# LEDChaser_Schemtic-P1_2025-11-05.net
KiCad netlist of a schematic drawn in EasyEDA Pro
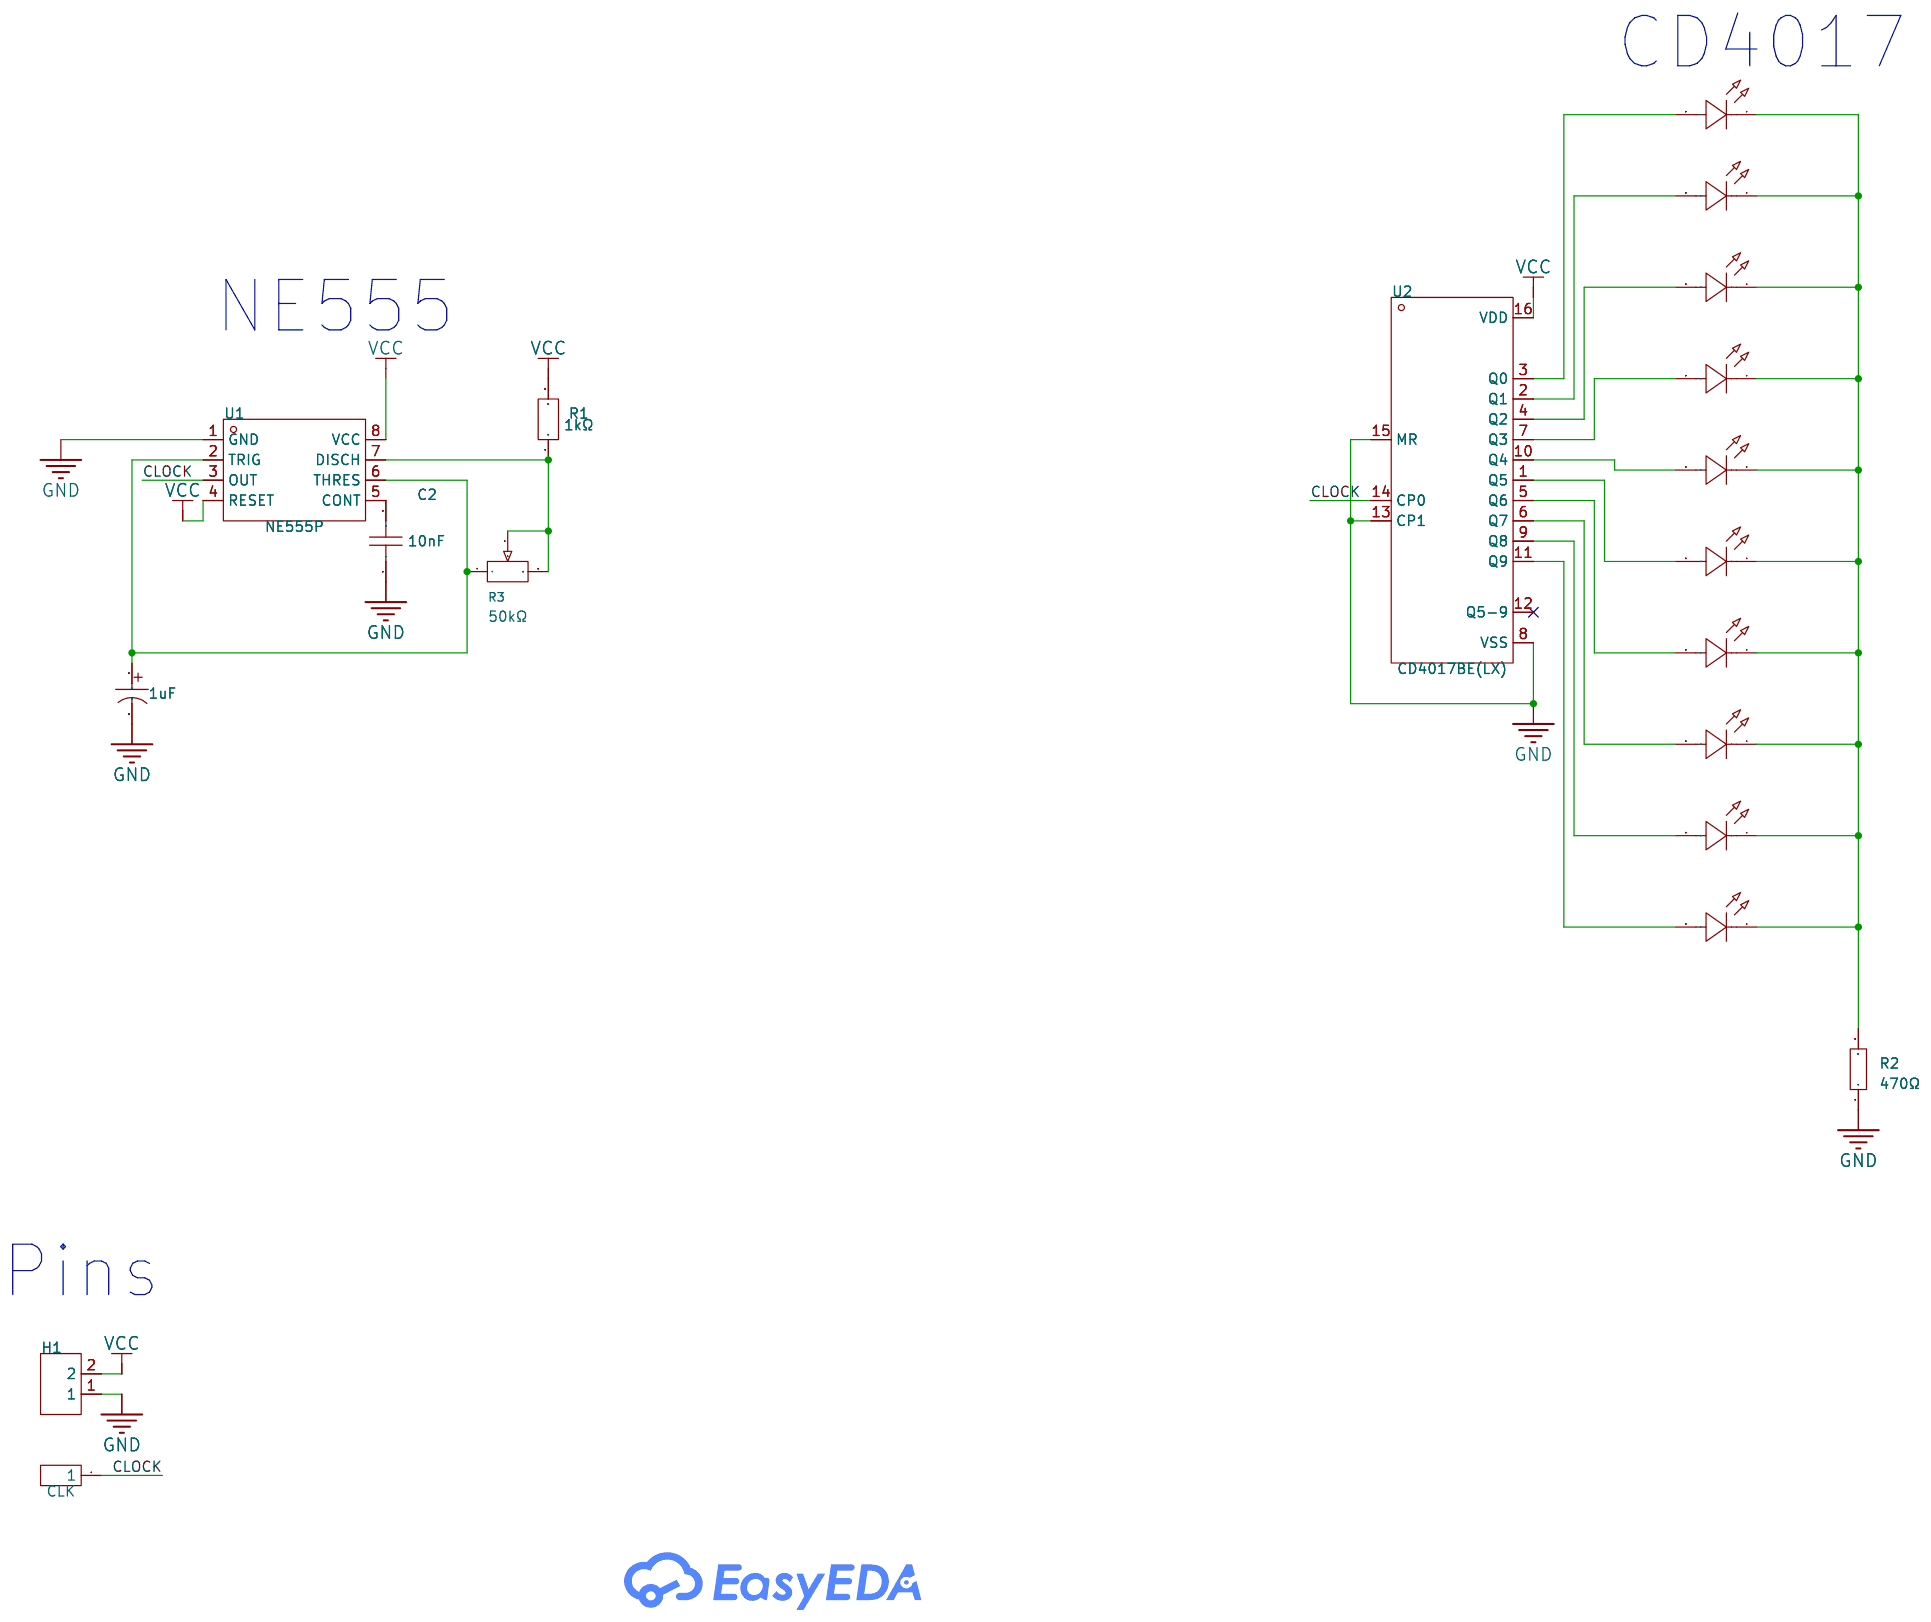
[diagram p0: schematic sheet]

(export (version "E")
  (design (tool "Eeschema 10.0.6"))
  (components
    (comp (ref "C1")
      (value "1uF")
      (footprint "easyedapro:CAP-TH_BD5.0-P2.00-D0.8-FD")
      (fields (field (name "Manufacturer Part") "KF010M050C110A") (field (name "Manufacturer") "CapXon(丰宾)"))
      (libsource (lib "easyedapro") (part "KF010M050C110A"))
    )
    (comp (ref "C2")
      (value "10nF")
      (footprint "easyedapro:CAP-TH_L8.0-W4.0-P5.00-D1.2")
      (fields (field (name "Manufacturer Part") "N09F1B103MN0B0S0N0") (field (name "Manufacturer") "STE(松田)"))
      (libsource (lib "easyedapro") (part "N09F1B103MN0B0S0N0"))
    )
    (comp (ref "H1")
      (value "PZ254V-11-02P")
      (footprint "easyedapro:HDR-TH_2P-P2.54-V-M")
      (fields (field (name "Manufacturer") "XFCN(兴飞)"))
      (libsource (lib "easyedapro") (part "PZ254V-11-02P"))
    )
    (comp (ref "LED1")
      (value "XL-502UWC")
      (footprint "easyedapro:LED-TH_BD5.9-P2.54-RD_WHITE")
      (fields (field (name "Manufacturer") "XINGLIGHT(成兴光)"))
      (libsource (lib "easyedapro") (part "XL-502UWC"))
    )
    (comp (ref "LED2")
      (value "XL-502UWC")
      (footprint "easyedapro:LED-TH_BD5.9-P2.54-RD_WHITE")
      (fields (field (name "Manufacturer") "XINGLIGHT(成兴光)"))
      (libsource (lib "easyedapro") (part "XL-502UWC"))
    )
    (comp (ref "LED3")
      (value "XL-502UWC")
      (footprint "easyedapro:LED-TH_BD5.9-P2.54-RD_WHITE")
      (fields (field (name "Manufacturer") "XINGLIGHT(成兴光)"))
      (libsource (lib "easyedapro") (part "XL-502UWC"))
    )
    (comp (ref "LED4")
      (value "XL-502UWC")
      (footprint "easyedapro:LED-TH_BD5.9-P2.54-RD_WHITE")
      (fields (field (name "Manufacturer") "XINGLIGHT(成兴光)"))
      (libsource (lib "easyedapro") (part "XL-502UWC"))
    )
    (comp (ref "LED5")
      (value "XL-502UWC")
      (footprint "easyedapro:LED-TH_BD5.9-P2.54-RD_WHITE")
      (fields (field (name "Manufacturer") "XINGLIGHT(成兴光)"))
      (libsource (lib "easyedapro") (part "XL-502UWC"))
    )
    (comp (ref "LED6")
      (value "XL-502UWC")
      (footprint "easyedapro:LED-TH_BD5.9-P2.54-RD_WHITE")
      (fields (field (name "Manufacturer") "XINGLIGHT(成兴光)"))
      (libsource (lib "easyedapro") (part "XL-502UWC"))
    )
    (comp (ref "LED7")
      (value "XL-502UWC")
      (footprint "easyedapro:LED-TH_BD5.9-P2.54-RD_WHITE")
      (fields (field (name "Manufacturer") "XINGLIGHT(成兴光)"))
      (libsource (lib "easyedapro") (part "XL-502UWC"))
    )
    (comp (ref "LED8")
      (value "XL-502UWC")
      (footprint "easyedapro:LED-TH_BD5.9-P2.54-RD_WHITE")
      (fields (field (name "Manufacturer") "XINGLIGHT(成兴光)"))
      (libsource (lib "easyedapro") (part "XL-502UWC"))
    )
    (comp (ref "LED9")
      (value "XL-502UWC")
      (footprint "easyedapro:LED-TH_BD5.9-P2.54-RD_WHITE")
      (fields (field (name "Manufacturer") "XINGLIGHT(成兴光)"))
      (libsource (lib "easyedapro") (part "XL-502UWC"))
    )
    (comp (ref "LED10")
      (value "XL-502UWC")
      (footprint "easyedapro:LED-TH_BD5.9-P2.54-RD_WHITE")
      (fields (field (name "Manufacturer") "XINGLIGHT(成兴光)"))
      (libsource (lib "easyedapro") (part "XL-502UWC"))
    )
    (comp (ref "P1")
      (value "CLK")
      (footprint "easyedapro:HDR-TH_1P-P2.54-V-M")
      (fields (field (name "Manufacturer Part") "2.54-1*1P针") (field (name "Manufacturer") "BOOMELE(博穆精密)"))
      (libsource (lib "easyedapro") (part "Header-Male-2.54_1x1"))
    )
    (comp (ref "R1")
      (value "1kΩ")
      (footprint "easyedapro:RES-TH_BD2.3-L6.5-P10.50-D0.5")
      (fields (field (name "Manufacturer Part") "MF1/4W-1KΩ±1%T52") (field (name "Manufacturer") "华星机电"))
      (libsource (lib "easyedapro") (part "MF1/4W-1KΩ±1%T52"))
    )
    (comp (ref "R2")
      (value "470Ω")
      (footprint "easyedapro:RES-TH_BD2.2-L6.5-P10.50-D0.6")
      (fields
        (field (name "Manufacturer Part") "MFR0W4F4700A50")
        (field (name "Manufacturer") "UNI-ROYAL(厚声)")
      )
      (libsource (lib "easyedapro") (part "MFR0W4F4700A50"))
    )
    (comp (ref "R3")
      (value "50kΩ")
      (footprint "easyedapro:RES-ADJ-TH_3P-L9.5-W4.85-P2.50-BL-L")
      (fields (field (name "Manufacturer Part") "3296X-1-503") (field (name "Manufacturer") "BOCHEN(博晨)"))
      (libsource (lib "easyedapro") (part "3296X-1-503_C118912"))
    )
    (comp (ref "U1")
      (value "NE555P")
      (footprint "easyedapro:DIP-8_L9.8-W6.6-P2.54-LS7.6-BL")
      (fields (field (name "Manufacturer") "TI(德州仪器)"))
      (libsource (lib "easyedapro") (part "NE555P"))
    )
    (comp (ref "U2")
      (value "CD4017BE(LX)")
      (footprint "easyedapro:PDIP-16_L19.3-W6.4-P2.54-LS7.94-BL")
      (fields (field (name "Manufacturer") "LX(灵星芯微)"))
      (libsource (lib "easyedapro") (part "CD4017BE(LX)"))
    )
  )
  (nets
    (net (code "1") (name "/CLOCK") (class "Default")
      (node (ref "P1") (pin "1") (pinfunction "1_1") (pintype "input"))
      (node (ref "U1") (pin "3") (pinfunction "OUT_3") (pintype "input"))
      (node (ref "U2") (pin "14") (pinfunction "CP0_14") (pintype "unspecified"))
    )
    (net (code "2") (name "GND") (class "Default")
      (node (ref "C1") (pin "2") (pinfunction "2_2") (pintype "input"))
      (node (ref "C2") (pin "1") (pinfunction "1_1") (pintype "unspecified"))
      (node (ref "H1") (pin "1") (pinfunction "1_1") (pintype "unspecified"))
      (node (ref "R2") (pin "1") (pinfunction "1_1") (pintype "input"))
      (node (ref "U1") (pin "1") (pinfunction "GND_1") (pintype "input"))
      (node (ref "U2") (pin "13") (pinfunction "CP1_13") (pintype "unspecified"))
      (node (ref "U2") (pin "15") (pinfunction "MR_15") (pintype "unspecified"))
      (node (ref "U2") (pin "8") (pinfunction "VSS_8") (pintype "unspecified"))
    )
    (net (code "3") (name "Net-(LED1-A)") (class "Default")
      (node (ref "LED1") (pin "2") (pinfunction "A_2") (pintype "unspecified"))
      (node (ref "U2") (pin "3") (pinfunction "Q0_3") (pintype "unspecified"))
    )
    (net (code "4") (name "Net-(LED1-K)") (class "Default")
      (node (ref "LED1") (pin "1") (pinfunction "K_1") (pintype "unspecified"))
      (node (ref "LED10") (pin "1") (pinfunction "K_1") (pintype "unspecified"))
      (node (ref "LED2") (pin "1") (pinfunction "K_1") (pintype "unspecified"))
      (node (ref "LED3") (pin "1") (pinfunction "K_1") (pintype "unspecified"))
      (node (ref "LED4") (pin "1") (pinfunction "K_1") (pintype "unspecified"))
      (node (ref "LED5") (pin "1") (pinfunction "K_1") (pintype "unspecified"))
      (node (ref "LED6") (pin "1") (pinfunction "K_1") (pintype "unspecified"))
      (node (ref "LED7") (pin "1") (pinfunction "K_1") (pintype "unspecified"))
      (node (ref "LED8") (pin "1") (pinfunction "K_1") (pintype "unspecified"))
      (node (ref "LED9") (pin "1") (pinfunction "K_1") (pintype "unspecified"))
      (node (ref "R2") (pin "2") (pinfunction "2_2") (pintype "input"))
    )
    (net (code "5") (name "Net-(LED2-A)") (class "Default")
      (node (ref "LED2") (pin "2") (pinfunction "A_2") (pintype "unspecified"))
      (node (ref "U2") (pin "2") (pinfunction "Q1_2") (pintype "unspecified"))
    )
    (net (code "6") (name "Net-(LED3-A)") (class "Default")
      (node (ref "LED3") (pin "2") (pinfunction "A_2") (pintype "unspecified"))
      (node (ref "U2") (pin "4") (pinfunction "Q2_4") (pintype "unspecified"))
    )
    (net (code "7") (name "Net-(LED4-A)") (class "Default")
      (node (ref "LED4") (pin "2") (pinfunction "A_2") (pintype "unspecified"))
      (node (ref "U2") (pin "10") (pinfunction "Q4_10") (pintype "unspecified"))
    )
    (net (code "8") (name "Net-(LED5-A)") (class "Default")
      (node (ref "LED5") (pin "2") (pinfunction "A_2") (pintype "unspecified"))
      (node (ref "U2") (pin "5") (pinfunction "Q6_5") (pintype "unspecified"))
    )
    (net (code "9") (name "Net-(LED6-A)") (class "Default")
      (node (ref "LED6") (pin "2") (pinfunction "A_2") (pintype "unspecified"))
      (node (ref "U2") (pin "6") (pinfunction "Q7_6") (pintype "unspecified"))
    )
    (net (code "10") (name "Net-(LED7-A)") (class "Default")
      (node (ref "LED7") (pin "2") (pinfunction "A_2") (pintype "unspecified"))
      (node (ref "U2") (pin "9") (pinfunction "Q8_9") (pintype "unspecified"))
    )
    (net (code "11") (name "Net-(LED8-A)") (class "Default")
      (node (ref "LED8") (pin "2") (pinfunction "A_2") (pintype "unspecified"))
      (node (ref "U2") (pin "11") (pinfunction "Q9_11") (pintype "unspecified"))
    )
    (net (code "12") (name "Net-(LED9-A)") (class "Default")
      (node (ref "LED9") (pin "2") (pinfunction "A_2") (pintype "unspecified"))
      (node (ref "U2") (pin "7") (pinfunction "Q3_7") (pintype "unspecified"))
    )
    (net (code "13") (name "Net-(LED10-A)") (class "Default")
      (node (ref "LED10") (pin "2") (pinfunction "A_2") (pintype "unspecified"))
      (node (ref "U2") (pin "1") (pinfunction "Q5_1") (pintype "unspecified"))
    )
    (net (code "14") (name "Net-(U1-CONT)") (class "Default")
      (node (ref "C2") (pin "2") (pinfunction "2_2") (pintype "unspecified"))
      (node (ref "U1") (pin "5") (pinfunction "CONT_5") (pintype "input"))
    )
    (net (code "15") (name "Net-(U1-DISCH)") (class "Default")
      (node (ref "R1") (pin "1") (pinfunction "1_1") (pintype "unspecified"))
      (node (ref "R3") (pin "2") (pinfunction "2_2") (pintype "input"))
      (node (ref "R3") (pin "3") (pinfunction "3_3") (pintype "input"))
      (node (ref "U1") (pin "7") (pinfunction "DISCH_7") (pintype "input"))
    )
    (net (code "16") (name "Net-(U1-THRES)") (class "Default")
      (node (ref "C1") (pin "1") (pinfunction "1_1") (pintype "input"))
      (node (ref "R3") (pin "1") (pinfunction "1_1") (pintype "input"))
      (node (ref "U1") (pin "2") (pinfunction "TRIG_2") (pintype "input"))
      (node (ref "U1") (pin "6") (pinfunction "THRES_6") (pintype "input"))
    )
    (net (code "17") (name "VCC") (class "Default")
      (node (ref "H1") (pin "2") (pinfunction "2_2") (pintype "unspecified"))
      (node (ref "R1") (pin "2") (pinfunction "2_2") (pintype "unspecified"))
      (node (ref "U1") (pin "4") (pinfunction "RESET_4") (pintype "input"))
      (node (ref "U1") (pin "8") (pinfunction "VCC_8") (pintype "input"))
      (node (ref "U2") (pin "16") (pinfunction "VDD_16") (pintype "unspecified"))
    )
    (net (code "18") (name "unconnected-(U2-Q5-9-Pad12)") (class "Default")
      (node (ref "U2") (pin "12") (pinfunction "Q5-9_12") (pintype "unspecified+no_connect"))
    )
  )
)
